# CF_Title.net
KiCad netlist of a schematic drawn in Altium Designer
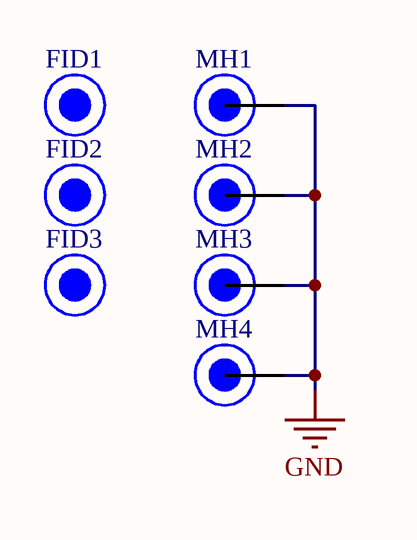
[diagram p0: CF_Title.SchDoc]

(export (version "E")
  (design (tool "Eeschema 10.0.6"))
  (components
    (comp (ref "FID1")
      (value "Fiducial 1mm")
      (footprint "FID_1MM")
      (description "FID - 1MM")
      (fields (field (name "CREATEDBY") "Jonathan Bouchard") (field (name "VERIFIEDBY") "Alexandre Imbeault"))
      (libsource (lib "S7CAS_Lib2019_REV1_00") (part "FID_1MM"))
    )
    (comp (ref "FID2")
      (value "Fiducial 1mm")
      (footprint "FID_1MM")
      (description "FID - 1MM")
      (fields (field (name "CREATEDBY") "Jonathan Bouchard") (field (name "VERIFIEDBY") "Alexandre Imbeault"))
      (libsource (lib "S7CAS_Lib2019_REV1_00") (part "FID_1MM"))
    )
    (comp (ref "FID3")
      (value "Fiducial 1mm")
      (footprint "FID_1MM")
      (description "FID - 1MM")
      (fields (field (name "CREATEDBY") "Jonathan Bouchard") (field (name "VERIFIEDBY") "Alexandre Imbeault"))
      (libsource (lib "S7CAS_Lib2019_REV1_00") (part "FID_1MM"))
    )
    (comp (ref "MH1")
      (value "Mounting Hole 6-32")
      (footprint "MH_ENG_6-32")
      (description "MH - Mounting Hole 6-32")
      (fields (field (name "CREATEDBY") "Jonathan Bouchard") (field (name "VERIFIEDBY") "Alexandre Imbeault"))
      (libsource (lib "S7CAS_Lib2019_REV1_00") (part "MH_6-32"))
    )
    (comp (ref "MH2")
      (value "Mounting Hole 6-32")
      (footprint "MH_ENG_6-32")
      (description "MH - Mounting Hole 6-32")
      (fields (field (name "CREATEDBY") "Jonathan Bouchard") (field (name "VERIFIEDBY") "Alexandre Imbeault"))
      (libsource (lib "S7CAS_Lib2019_REV1_00") (part "MH_6-32"))
    )
    (comp (ref "MH3")
      (value "Mounting Hole 6-32")
      (footprint "MH_ENG_6-32")
      (description "MH - Mounting Hole 6-32")
      (fields (field (name "CREATEDBY") "Jonathan Bouchard") (field (name "VERIFIEDBY") "Alexandre Imbeault"))
      (libsource (lib "S7CAS_Lib2019_REV1_00") (part "MH_6-32"))
    )
    (comp (ref "MH4")
      (value "Mounting Hole 6-32")
      (footprint "MH_ENG_6-32")
      (description "MH - Mounting Hole 6-32")
      (fields (field (name "CREATEDBY") "Jonathan Bouchard") (field (name "VERIFIEDBY") "Alexandre Imbeault"))
      (libsource (lib "S7CAS_Lib2019_REV1_00") (part "MH_6-32"))
    )
  )
  (nets
    (net (code "1") (name "GND") (class "Default")
      (node (ref "MH1") (pin "1") (pinfunction "1_1") (pintype "passive"))
      (node (ref "MH2") (pin "1") (pinfunction "1_1") (pintype "passive"))
      (node (ref "MH3") (pin "1") (pinfunction "1_1") (pintype "passive"))
      (node (ref "MH4") (pin "1") (pinfunction "1_1") (pintype "passive"))
    )
  )
)
